# comms_vhf.net
KiCad netlist of a schematic drawn in Altium Designer
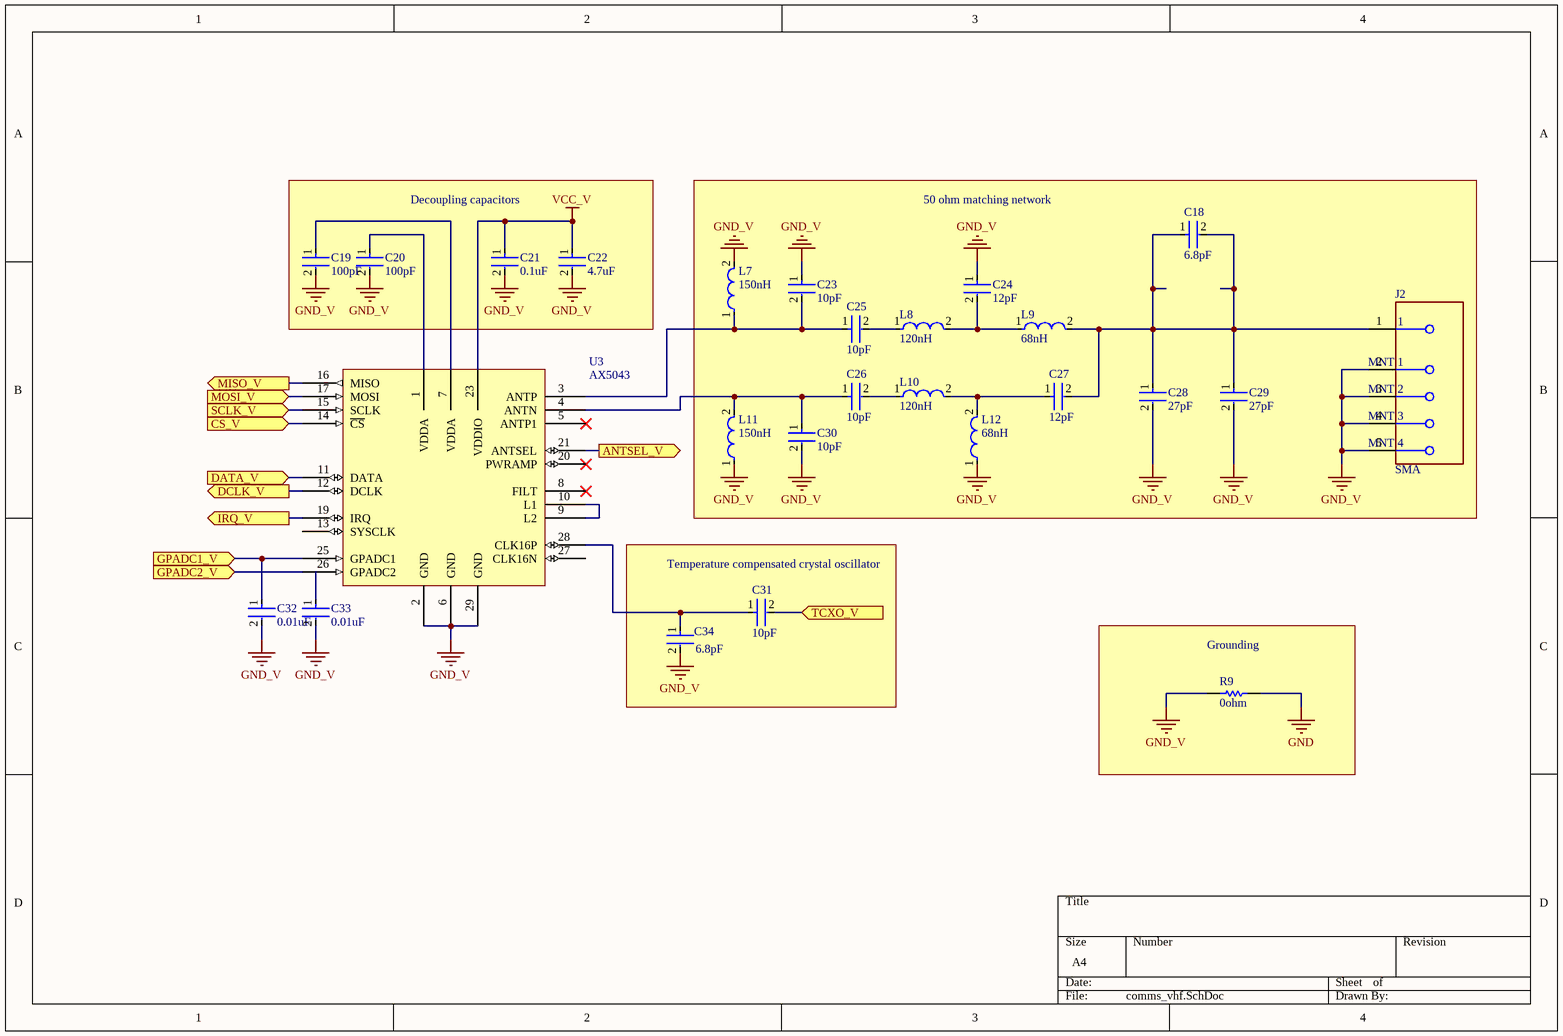
[diagram p0: comms_vhf.SchDoc]

(export (version "E")
  (design (tool "Eeschema 10.0.6"))
  (components
    (comp (ref "C18")
      (value "6.8pF")
      (footprint "FP-C0805C-DN-IPC_A")
      (description "Cap Ceramic 6.8pF 50V C0G 0.5pF SMD 0805 125°C Plastic T/R")
      (fields
        (field (name "MANUFACTURER") "KEMET")
        (field (name "MANUFACTURER PART NUMBER") "C0805C689D5GACTU")
      )
      (libsource (lib "WEST_Schematic_Library") (part "C0805C689D5GACTU"))
    )
    (comp (ref "C19")
      (value "100pF")
      (footprint "FP-C0805C-DN-IPC_A")
      (description "Multilayer Ceramic Capacitors (MLCC) - SMD/SMT 100volts 100pF C0G 5%")
      (fields
        (field (name "MANUFACTURER") "KEMET")
        (field (name "MANUFACTURER PART NUMBER") "C0805C101J1GACTU")
      )
      (libsource (lib "WEST_Schematic_Library") (part "C0805C101J1GACTU"))
    )
    (comp (ref "C20")
      (value "100pF")
      (footprint "FP-C0805C-DN-IPC_A")
      (description "Multilayer Ceramic Capacitors (MLCC) - SMD/SMT 100volts 100pF C0G 5%")
      (fields
        (field (name "MANUFACTURER") "KEMET")
        (field (name "MANUFACTURER PART NUMBER") "C0805C101J1GACTU")
      )
      (libsource (lib "WEST_Schematic_Library") (part "C0805C101J1GACTU"))
    )
    (comp (ref "C21")
      (value "0.1uF")
      (footprint "FP-C0805C-DN-IPC_A")
      (description "Cap Ceramic 0.1uF 50V X7R 10% SMD 2.0 x 1.2 mm 125 C Paper T/R")
      (fields
        (field (name "MANUFACTURER") "KEMET")
        (field (name "MANUFACTURER PART NUMBER") "C0805C104K5RACTU")
      )
      (libsource (lib "WEST_Schematic_Library") (part "C0805C104K5RACTU"))
    )
    (comp (ref "C22")
      (value "4.7uF")
      (footprint "FP-C0805C-DN-IPC_A")
      (description "Cap Ceramic 4.7uF 25V X5R 10% SMD 0805 85°C Plastic T/R")
      (fields
        (field (name "MANUFACTURER") "KEMET")
        (field (name "MANUFACTURER PART NUMBER") "C0805C475K3PACTU")
      )
      (libsource (lib "WEST_Schematic_Library") (part "C0805C475K3PACTU"))
    )
    (comp (ref "C23")
      (value "10pF")
      (footprint "FP-C0805C-DN-IPC_A")
      (description "Cap Ceramic 10pF 100V C0G 5% SMD 0805 125C Plastic T/R")
      (fields
        (field (name "MANUFACTURER") "KEMET")
        (field (name "MANUFACTURER PART NUMBER") "C0805C100J1GACTU")
      )
      (libsource (lib "WEST_Schematic_Library") (part "C0805C100J1GACTU"))
    )
    (comp (ref "C24")
      (value "12pF")
      (footprint "FP-C0805C-DN-IPC_A")
      (description "0805 C 12pF Ceramic Multilayer Capacitor; 50 VDC; +125degC; C0G Dielec; +/-5%")
      (fields
        (field (name "MANUFACTURER") "KEMET")
        (field (name "MANUFACTURER PART NUMBER") "C0805C120J5GACTU")
      )
      (libsource (lib "WEST_Schematic_Library") (part "C0805C120J5GACTU"))
    )
    (comp (ref "C25")
      (value "10pF")
      (footprint "FP-C0805C-DN-IPC_A")
      (description "Cap Ceramic 10pF 100V C0G 5% SMD 0805 125C Plastic T/R")
      (fields
        (field (name "MANUFACTURER") "KEMET")
        (field (name "MANUFACTURER PART NUMBER") "C0805C100J1GACTU")
      )
      (libsource (lib "WEST_Schematic_Library") (part "C0805C100J1GACTU"))
    )
    (comp (ref "C26")
      (value "10pF")
      (footprint "FP-C0805C-DN-IPC_A")
      (description "Cap Ceramic 10pF 100V C0G 5% SMD 0805 125C Plastic T/R")
      (fields
        (field (name "MANUFACTURER") "KEMET")
        (field (name "MANUFACTURER PART NUMBER") "C0805C100J1GACTU")
      )
      (libsource (lib "WEST_Schematic_Library") (part "C0805C100J1GACTU"))
    )
    (comp (ref "C27")
      (value "12pF")
      (footprint "FP-C0805C-DN-IPC_A")
      (description "0805 C 12pF Ceramic Multilayer Capacitor; 50 VDC; +125degC; C0G Dielec; +/-5%")
      (fields
        (field (name "MANUFACTURER") "KEMET")
        (field (name "MANUFACTURER PART NUMBER") "C0805C120J5GACTU")
      )
      (libsource (lib "WEST_Schematic_Library") (part "C0805C120J5GACTU"))
    )
    (comp (ref "C28")
      (value "27pF")
      (footprint "FP-C0805C-DN-IPC_A")
      (description "Cap Ceramic 27pF ±5% 50V C0G, NP0 0805")
      (fields
        (field (name "MANUFACTURER") "KEMET")
        (field (name "MANUFACTURER PART NUMBER") "C0805C270J5GACTU")
      )
      (libsource (lib "WEST_Schematic_Library") (part "C0805C270J5GACTU"))
    )
    (comp (ref "C29")
      (value "27pF")
      (footprint "FP-C0805C-DN-IPC_A")
      (description "Cap Ceramic 27pF ±5% 50V C0G, NP0 0805")
      (fields
        (field (name "MANUFACTURER") "KEMET")
        (field (name "MANUFACTURER PART NUMBER") "C0805C270J5GACTU")
      )
      (libsource (lib "WEST_Schematic_Library") (part "C0805C270J5GACTU"))
    )
    (comp (ref "C30")
      (value "10pF")
      (footprint "FP-C0805C-DN-IPC_A")
      (description "Cap Ceramic 10pF 100V C0G 5% SMD 0805 125C Plastic T/R")
      (fields
        (field (name "MANUFACTURER") "KEMET")
        (field (name "MANUFACTURER PART NUMBER") "C0805C100J1GACTU")
      )
      (libsource (lib "WEST_Schematic_Library") (part "C0805C100J1GACTU"))
    )
    (comp (ref "C31")
      (value "10pF")
      (footprint "FP-C0805C-DN-IPC_A")
      (description "Cap Ceramic 10pF 100V C0G 5% SMD 0805 125C Plastic T/R")
      (fields
        (field (name "MANUFACTURER") "KEMET")
        (field (name "MANUFACTURER PART NUMBER") "C0805C100J1GACTU")
      )
      (libsource (lib "WEST_Schematic_Library") (part "C0805C100J1GACTU"))
    )
    (comp (ref "C32")
      (value "0.01uF")
      (footprint "FP-C0805C-DN-IPC_A")
      (description "Cap Ceramic 0.01uF 50V X7R 10% SMD 0805 125C Plastic T/R")
      (fields
        (field (name "MANUFACTURER") "KEMET")
        (field (name "MANUFACTURER PART NUMBER") "C0805C103K5RAC-TU")
      )
      (libsource (lib "WEST_Schematic_Library") (part "C0805C103K5RAC-TU"))
    )
    (comp (ref "C33")
      (value "0.01uF")
      (footprint "FP-C0805C-DN-IPC_A")
      (description "Cap Ceramic 0.01uF 50V X7R 10% SMD 0805 125C Plastic T/R")
      (fields
        (field (name "MANUFACTURER") "KEMET")
        (field (name "MANUFACTURER PART NUMBER") "C0805C103K5RAC-TU")
      )
      (libsource (lib "WEST_Schematic_Library") (part "C0805C103K5RAC-TU"))
    )
    (comp (ref "C34")
      (value "6.8pF")
      (footprint "FP-C0805C-DN-IPC_A")
      (description "Cap Ceramic 6.8pF 50V C0G 0.5pF SMD 0805 125°C Plastic T/R")
      (fields
        (field (name "MANUFACTURER") "KEMET")
        (field (name "MANUFACTURER PART NUMBER") "C0805C689D5GACTU")
      )
      (libsource (lib "WEST_Schematic_Library") (part "C0805C689D5GACTU"))
    )
    (comp (ref "J2")
      (value "SMA")
      (footprint "FP-73251-1350-MFG")
      (description "RF Connectors / Coaxial Connectors SMA ST PCB-JCK STD SMT")
      (fields (field (name "MANUFACTURER") "Molex") (field (name "MANUFACTURER PART NUMBER") "73251-1350"))
      (libsource (lib "WEST_Schematic_Library") (part "73251-1350"))
    )
    (comp (ref "L7")
      (value "150nH")
      (footprint "FP-C0805C-DN-IPC_A")
      (description "Ind RF Chip Wirewound 150nH 5% 100MHz 50Q-Factor 400mA 0805 Embossed T/R")
      (fields
        (field (name "MANUFACTURER") "Murata")
        (field (name "MANUFACTURER PART NUMBER") "LQW2BASR15J00L")
      )
      (libsource (lib "WEST_Schematic_Library") (part "LQW2BASR15J00L"))
    )
    (comp (ref "L8")
      (value "120nH")
      (footprint "FP-C0805C-DN-IPC_A")
      (description "Inductor RF Chip Wirewound 120nH 5% 100MHz 40Q-Factor Air 320mA 400mOhm DCR 0805 Embossed T/R")
      (fields
        (field (name "MANUFACTURER") "Murata")
        (field (name "MANUFACTURER PART NUMBER") "LQW2BHNR12J03L")
      )
      (libsource (lib "WEST_Schematic_Library") (part "LQW2BHNR12J03L"))
    )
    (comp (ref "L9")
      (value "68nH")
      (footprint "FP-C0805C-DN-IPC_A")
      (description "Ind RF Chip Wirewound 68nH 5% 200MHz 60Q-Factor 500mA 0805 Embossed T/R")
      (fields
        (field (name "MANUFACTURER") "Murata")
        (field (name "MANUFACTURER PART NUMBER") "LQW2BAS68NJ00L")
      )
      (libsource (lib "WEST_Schematic_Library") (part "LQW2BAS68NJ00L"))
    )
    (comp (ref "L10")
      (value "120nH")
      (footprint "FP-C0805C-DN-IPC_A")
      (description "Inductor RF Chip Wirewound 120nH 5% 100MHz 40Q-Factor Air 320mA 400mOhm DCR 0805 Embossed T/R")
      (fields
        (field (name "MANUFACTURER") "Murata")
        (field (name "MANUFACTURER PART NUMBER") "LQW2BHNR12J03L")
      )
      (libsource (lib "WEST_Schematic_Library") (part "LQW2BHNR12J03L"))
    )
    (comp (ref "L11")
      (value "150nH")
      (footprint "FP-C0805C-DN-IPC_A")
      (description "Ind RF Chip Wirewound 150nH 5% 100MHz 50Q-Factor 400mA 0805 Embossed T/R")
      (fields
        (field (name "MANUFACTURER") "Murata")
        (field (name "MANUFACTURER PART NUMBER") "LQW2BASR15J00L")
      )
      (libsource (lib "WEST_Schematic_Library") (part "LQW2BASR15J00L"))
    )
    (comp (ref "L12")
      (value "68nH")
      (footprint "FP-C0805C-DN-IPC_A")
      (description "Ind RF Chip Wirewound 68nH 5% 200MHz 60Q-Factor 500mA 0805 Embossed T/R")
      (fields
        (field (name "MANUFACTURER") "Murata")
        (field (name "MANUFACTURER PART NUMBER") "LQW2BAS68NJ00L")
      )
      (libsource (lib "WEST_Schematic_Library") (part "LQW2BAS68NJ00L"))
    )
    (comp (ref "R9")
      (value "0ohm")
      (footprint "FP-C0805C-DN-IPC_A")
      (description "CRCW Series 0805 0.125 W 0 Ohm Jumper Surface Mount Thick Film Chip Resistor")
      (fields
        (field (name "MANUFACTURER") "Vishay")
        (field (name "MANUFACTURER PART NUMBER") "CRCW08050000Z0EA")
      )
      (libsource (lib "WEST_Schematic_Library") (part "CRCW08050000Z0EA"))
    )
    (comp (ref "U3")
      (value "AX5043")
      (footprint "QFN50P500X500X90_HS-29N")
      (description "Rf Transceiver ASK/AFSK/FM/FSK/4-FSK/GFSK/GMSK/MSK/PSK 1.8 V to 3.6V 28-PIN QFN T/r")
      (fields
        (field (name "MANUFACTURER") "ON Semiconductor")
        (field (name "MANUFACTURER PART NUMBER") "AX5043-1-TW30")
      )
      (libsource (lib "WEST_Schematic_Library") (part "AX5043-1-TW30"))
    )
  )
  (nets
    (net (code "1") (name "/ANTSEL_V") (class "Default")
      (node (ref "U3") (pin "21") (pinfunction "ANTSEL_21") (pintype "bidirectional"))
    )
    (net (code "2") (name "/CS_V") (class "Default")
      (node (ref "U3") (pin "14") (pinfunction "~{CS}_14") (pintype "input"))
    )
    (net (code "3") (name "/DATA_V") (class "Default")
      (node (ref "U3") (pin "11") (pinfunction "DATA_11") (pintype "bidirectional"))
    )
    (net (code "4") (name "/DCLK_V") (class "Default")
      (node (ref "U3") (pin "12") (pinfunction "DCLK_12") (pintype "bidirectional"))
    )
    (net (code "5") (name "/GPADC1_V") (class "Default")
      (node (ref "C32") (pin "1") (pinfunction "1_1") (pintype "passive"))
      (node (ref "U3") (pin "25") (pinfunction "GPADC1_25") (pintype "input"))
    )
    (net (code "6") (name "/GPADC2_V") (class "Default")
      (node (ref "U3") (pin "26") (pinfunction "GPADC2_26") (pintype "input"))
    )
    (net (code "7") (name "/IRQ_V") (class "Default")
      (node (ref "U3") (pin "19") (pinfunction "IRQ_19") (pintype "bidirectional"))
    )
    (net (code "8") (name "/MISO_V") (class "Default")
      (node (ref "U3") (pin "16") (pinfunction "MISO_16") (pintype "output"))
    )
    (net (code "9") (name "/MOSI_V") (class "Default")
      (node (ref "U3") (pin "17") (pinfunction "MOSI_17") (pintype "input"))
    )
    (net (code "10") (name "/SCLK_V") (class "Default")
      (node (ref "U3") (pin "15") (pinfunction "SCLK_15") (pintype "input"))
    )
    (net (code "11") (name "/TCXO_V") (class "Default")
      (node (ref "C31") (pin "2") (pinfunction "2_2") (pintype "passive"))
    )
    (net (code "12") (name "GND") (class "Default")
      (node (ref "R9") (pin "2") (pinfunction "2_2") (pintype "passive"))
    )
    (net (code "13") (name "GND_V") (class "Default")
      (node (ref "C19") (pin "2") (pinfunction "2_2") (pintype "passive"))
      (node (ref "C20") (pin "2") (pinfunction "2_2") (pintype "passive"))
      (node (ref "C21") (pin "2") (pinfunction "2_2") (pintype "passive"))
      (node (ref "C22") (pin "2") (pinfunction "2_2") (pintype "passive"))
      (node (ref "C23") (pin "1") (pinfunction "1_1") (pintype "passive"))
      (node (ref "C24") (pin "1") (pinfunction "1_1") (pintype "passive"))
      (node (ref "C28") (pin "2") (pinfunction "2_2") (pintype "passive"))
      (node (ref "C29") (pin "2") (pinfunction "2_2") (pintype "passive"))
      (node (ref "C30") (pin "2") (pinfunction "2_2") (pintype "passive"))
      (node (ref "C32") (pin "2") (pinfunction "2_2") (pintype "passive"))
      (node (ref "C33") (pin "2") (pinfunction "2_2") (pintype "passive"))
      (node (ref "C34") (pin "2") (pinfunction "2_2") (pintype "passive"))
      (node (ref "J2") (pin "2") (pinfunction "MNT_1_2") (pintype "passive"))
      (node (ref "J2") (pin "3") (pinfunction "MNT_2_3") (pintype "passive"))
      (node (ref "J2") (pin "4") (pinfunction "MNT_3_4") (pintype "passive"))
      (node (ref "J2") (pin "5") (pinfunction "MNT_4_5") (pintype "passive"))
      (node (ref "L11") (pin "1") (pinfunction "1_1") (pintype "passive"))
      (node (ref "L12") (pin "1") (pinfunction "1_1") (pintype "passive"))
      (node (ref "L7") (pin "2") (pinfunction "2_2") (pintype "passive"))
      (node (ref "R9") (pin "1") (pinfunction "1_1") (pintype "passive"))
      (node (ref "U3") (pin "2") (pinfunction "GND_2") (pintype "power_in"))
      (node (ref "U3") (pin "29") (pinfunction "GND_29") (pintype "power_in"))
      (node (ref "U3") (pin "6") (pinfunction "GND_6") (pintype "power_in"))
    )
    (net (code "14") (name "Net-(C18-Pad1)") (class "Default")
      (node (ref "C18") (pin "1") (pinfunction "1_1") (pintype "passive"))
      (node (ref "C18") (pin "2") (pinfunction "2_2") (pintype "passive"))
      (node (ref "C27") (pin "2") (pinfunction "2_2") (pintype "passive"))
      (node (ref "C28") (pin "1") (pinfunction "1_1") (pintype "passive"))
      (node (ref "C29") (pin "1") (pinfunction "1_1") (pintype "passive"))
      (node (ref "J2") (pin "1") (pinfunction "1_1") (pintype "passive"))
      (node (ref "L9") (pin "2") (pinfunction "2_2") (pintype "passive"))
    )
    (net (code "15") (name "Net-(C19-Pad1)") (class "Default")
      (node (ref "C19") (pin "1") (pinfunction "1_1") (pintype "passive"))
      (node (ref "U3") (pin "7") (pinfunction "VDDA_7") (pintype "power_in"))
    )
    (net (code "16") (name "Net-(C20-Pad1)") (class "Default")
      (node (ref "C20") (pin "1") (pinfunction "1_1") (pintype "passive"))
      (node (ref "U3") (pin "1") (pinfunction "VDDA_1") (pintype "power_in"))
    )
    (net (code "17") (name "Net-(C24-Pad2)") (class "Default")
      (node (ref "C24") (pin "2") (pinfunction "2_2") (pintype "passive"))
      (node (ref "L8") (pin "2") (pinfunction "2_2") (pintype "passive"))
      (node (ref "L9") (pin "1") (pinfunction "1_1") (pintype "passive"))
    )
    (net (code "18") (name "Net-(C25-Pad2)") (class "Default")
      (node (ref "C25") (pin "2") (pinfunction "2_2") (pintype "passive"))
      (node (ref "L8") (pin "1") (pinfunction "1_1") (pintype "passive"))
    )
    (net (code "19") (name "Net-(C26-Pad2)") (class "Default")
      (node (ref "C26") (pin "2") (pinfunction "2_2") (pintype "passive"))
      (node (ref "L10") (pin "1") (pinfunction "1_1") (pintype "passive"))
    )
    (net (code "20") (name "Net-(C27-Pad1)") (class "Default")
      (node (ref "C27") (pin "1") (pinfunction "1_1") (pintype "passive"))
      (node (ref "L10") (pin "2") (pinfunction "2_2") (pintype "passive"))
      (node (ref "L12") (pin "2") (pinfunction "2_2") (pintype "passive"))
    )
    (net (code "21") (name "Net-(U3-ANTN)") (class "Default")
      (node (ref "C26") (pin "1") (pinfunction "1_1") (pintype "passive"))
      (node (ref "C30") (pin "1") (pinfunction "1_1") (pintype "passive"))
      (node (ref "L11") (pin "2") (pinfunction "2_2") (pintype "passive"))
      (node (ref "U3") (pin "4") (pinfunction "ANTN_4") (pintype "passive"))
    )
    (net (code "22") (name "Net-(U3-ANTP)") (class "Default")
      (node (ref "C23") (pin "2") (pinfunction "2_2") (pintype "passive"))
      (node (ref "C25") (pin "1") (pinfunction "1_1") (pintype "passive"))
      (node (ref "L7") (pin "1") (pinfunction "1_1") (pintype "passive"))
      (node (ref "U3") (pin "3") (pinfunction "ANTP_3") (pintype "passive"))
    )
    (net (code "23") (name "Net-(U3-CLK16P)") (class "Default")
      (node (ref "C31") (pin "1") (pinfunction "1_1") (pintype "passive"))
      (node (ref "C34") (pin "1") (pinfunction "1_1") (pintype "passive"))
      (node (ref "U3") (pin "28") (pinfunction "CLK16P_28") (pintype "bidirectional"))
    )
    (net (code "24") (name "Net-(U3-L1)") (class "Default")
      (node (ref "U3") (pin "10") (pinfunction "L1_10") (pintype "passive"))
      (node (ref "U3") (pin "9") (pinfunction "L2_9") (pintype "passive"))
    )
    (net (code "25") (name "VCC_V") (class "Default")
      (node (ref "C21") (pin "1") (pinfunction "1_1") (pintype "passive"))
      (node (ref "C22") (pin "1") (pinfunction "1_1") (pintype "passive"))
      (node (ref "U3") (pin "23") (pinfunction "VDDIO_23") (pintype "power_in"))
    )
    (net (code "26") (name "unconnected-(C33-Pad1)") (class "Default")
      (node (ref "C33") (pin "1") (pinfunction "1_1") (pintype "passive"))
    )
    (net (code "27") (name "unconnected-(U3-ANTP1-Pad5)") (class "Default")
      (node (ref "U3") (pin "5") (pinfunction "ANTP1_5") (pintype "power_in+no_connect"))
    )
    (net (code "28") (name "unconnected-(U3-CLK16N-Pad27)") (class "Default")
      (node (ref "U3") (pin "27") (pinfunction "CLK16N_27") (pintype "bidirectional"))
    )
    (net (code "29") (name "unconnected-(U3-FILT-Pad8)") (class "Default")
      (node (ref "U3") (pin "8") (pinfunction "FILT_8") (pintype "passive+no_connect"))
    )
    (net (code "30") (name "unconnected-(U3-PWRAMP-Pad20)") (class "Default")
      (node (ref "U3") (pin "20") (pinfunction "PWRAMP_20") (pintype "bidirectional+no_connect"))
    )
    (net (code "31") (name "unconnected-(U3-SYSCLK-Pad13)") (class "Default")
      (node (ref "U3") (pin "13") (pinfunction "SYSCLK_13") (pintype "bidirectional"))
    )
  )
)
